# TinyDVR_Slave.net
KiCad netlist of a schematic drawn in Altium Designer
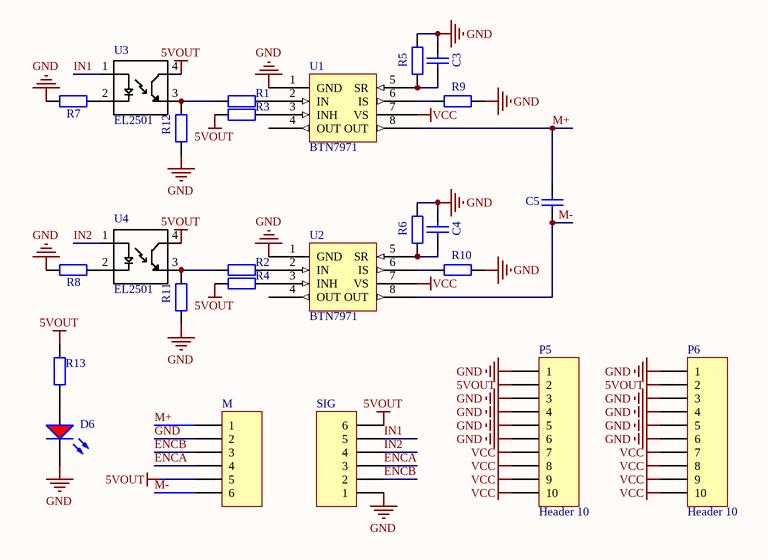
[diagram p0: TinyDVR_Slave.SchDoc]

(export (version "E")
  (design (tool "Eeschema 10.0.6"))
  (components
    (comp (ref "C3")
      (value "100nF (104) 10% 50V")
      (footprint "0603_C")
      (description "贴片电容")
      (libsource (lib "Miscellaneous Devices LC") (part "0603 100nF (104) 10% 50V"))
    )
    (comp (ref "C4")
      (value "100nF (104) 10% 50V")
      (footprint "0603_C")
      (description "贴片电容")
      (libsource (lib "Miscellaneous Devices LC") (part "0603 100nF (104) 10% 50V"))
    )
    (comp (ref "C5")
      (value "22pF (220) 5% 50V")
      (footprint "0603_C")
      (description "贴片电容")
      (libsource (lib "Miscellaneous Devices LC") (part "0603 22pF (220) 5% 50V"))
    )
    (comp (ref "D6")
      (value "红灯 0603")
      (footprint "0603_LED_S1")
      (description "发光二极管")
      (libsource (lib "Miscellaneous Devices LC") (part "0603 红灯"))
    )
    (comp (ref "M")
      (value "Header 6H")
      (footprint "HDR1X6H")
      (description "Header, 6-Pin, Right Angle")
      (fields (field (name "PUBLISHER") "Altium Limited"))
      (libsource (lib "") (part "Header 6H_1"))
    )
    (comp (ref "P5")
      (value "Header 10")
      (footprint "HDR1X10")
      (description "Header, 10-Pin")
      (fields (field (name "PUBLISHER") "Altium Limited"))
      (libsource (lib "Miscellaneous Connectors") (part "Header 10"))
    )
    (comp (ref "P6")
      (value "Header 10")
      (footprint "HDR1X10")
      (description "Header, 10-Pin")
      (fields (field (name "PUBLISHER") "Altium Limited"))
      (libsource (lib "Miscellaneous Connectors") (part "Header 10"))
    )
    (comp (ref "R1")
      (value "10KΩ (1002) ±1%")
      (footprint "0603_R")
      (description "贴片电阻")
      (libsource (lib "Miscellaneous Devices LC") (part "0603 10KΩ (1002) 1%"))
    )
    (comp (ref "R2")
      (value "10KΩ (1002) ±1%")
      (footprint "0603_R")
      (description "贴片电阻")
      (libsource (lib "Miscellaneous Devices LC") (part "0603 10KΩ (1002) 1%"))
    )
    (comp (ref "R3")
      (value "10KΩ (1002) ±1%")
      (footprint "0603_R")
      (description "贴片电阻")
      (libsource (lib "Miscellaneous Devices LC") (part "0603 10KΩ (1002) 1%"))
    )
    (comp (ref "R4")
      (value "10KΩ (1002) ±1%")
      (footprint "0603_R")
      (description "贴片电阻")
      (libsource (lib "Miscellaneous Devices LC") (part "0603 10KΩ (1002) 1%"))
    )
    (comp (ref "R5")
      (value "1KΩ (1001) ±1%")
      (footprint "0603_R")
      (description "贴片电阻")
      (libsource (lib "") (part "0603 1KΩ (1001) 1%_1"))
    )
    (comp (ref "R6")
      (value "1KΩ (1001) ±1%")
      (footprint "0603_R")
      (description "贴片电阻")
      (libsource (lib "") (part "0603 1KΩ (1001) 1%_1"))
    )
    (comp (ref "R7")
      (value "1KΩ (1001) ±1%")
      (footprint "0603_R")
      (description "贴片电阻")
      (libsource (lib "Miscellaneous Devices LC") (part "0603 1KΩ (1001) 1%"))
    )
    (comp (ref "R8")
      (value "1KΩ (1001) ±1%")
      (footprint "0603_R")
      (description "贴片电阻")
      (libsource (lib "Miscellaneous Devices LC") (part "0603 1KΩ (1001) 1%"))
    )
    (comp (ref "R9")
      (value "2KΩ (2001) ±1%")
      (footprint "0603_R")
      (description "贴片电阻")
      (libsource (lib "Miscellaneous Devices LC") (part "0603 2KΩ (2001) 1%"))
    )
    (comp (ref "R10")
      (value "2KΩ (2001) ±1%")
      (footprint "0603_R")
      (description "贴片电阻")
      (libsource (lib "Miscellaneous Devices LC") (part "0603 2KΩ (2001) 1%"))
    )
    (comp (ref "R11")
      (value "2KΩ (2001) ±1%")
      (footprint "0603_R")
      (description "贴片电阻")
      (libsource (lib "") (part "0603 2KΩ (2001) 1%_1"))
    )
    (comp (ref "R12")
      (value "2KΩ (2001) ±1%")
      (footprint "0603_R")
      (description "贴片电阻")
      (libsource (lib "") (part "0603 2KΩ (2001) 1%_1"))
    )
    (comp (ref "R13")
      (value "4.7k")
      (footprint "0603_R")
      (description "贴片电阻")
      (libsource (lib "Miscellaneous Devices LC") (part "0603 470Ω (4700) 1%"))
    )
    (comp (ref "SIG")
      (value "Header 6H")
      (footprint "HDR1X6H")
      (description "Header, 6-Pin, Right Angle")
      (fields (field (name "PUBLISHER") "Altium Limited"))
      (libsource (lib "Miscellaneous Connectors") (part "Header 6H"))
    )
    (comp (ref "U1")
      (value "BTN7971")
      (footprint "DPAK127P1615X127-8N")
      (libsource (lib "Sheet2") (part "BTN7971"))
    )
    (comp (ref "U2")
      (value "BTN7971")
      (footprint "DPAK127P1615X127-8N")
      (libsource (lib "Sheet2") (part "BTN7971"))
    )
    (comp (ref "U3")
      (value "EL2501")
      (footprint "*SOIC254P1030X390-4N_EL817S1(A)(TU)-V")
      (description "Optoisoltr 5kv Transistor 4-Smd")
      (fields (field (name "MF") "Everlight Electronics") (field (name "MP") "EL817S1_A__TU_-V"))
      (libsource (lib "altium-import") (part "root_0_EL817S1(A)(TU)-V_"))
    )
    (comp (ref "U4")
      (value "EL2501")
      (footprint "*SOIC254P1030X390-4N_EL817S1(A)(TU)-V")
      (description "Optoisoltr 5kv Transistor 4-Smd")
      (fields (field (name "MF") "Everlight Electronics") (field (name "MP") "EL817S1_A__TU_-V"))
      (libsource (lib "altium-import") (part "root_0_EL817S1(A)(TU)-V_"))
    )
  )
  (nets
    (net (code "1") (name "/ENCA") (class "Default")
      (node (ref "M") (pin "4") (pinfunction "4_4") (pintype "passive"))
      (node (ref "SIG") (pin "3") (pinfunction "3_3") (pintype "passive"))
    )
    (net (code "2") (name "/ENCB") (class "Default")
      (node (ref "M") (pin "3") (pinfunction "3_3") (pintype "passive"))
      (node (ref "SIG") (pin "2") (pinfunction "2_2") (pintype "passive"))
    )
    (net (code "3") (name "/IN1") (class "Default")
      (node (ref "SIG") (pin "5") (pinfunction "5_5") (pintype "passive"))
      (node (ref "U3") (pin "1") (pinfunction "A_1") (pintype "passive"))
    )
    (net (code "4") (name "/IN2") (class "Default")
      (node (ref "SIG") (pin "4") (pinfunction "4_4") (pintype "passive"))
      (node (ref "U4") (pin "1") (pinfunction "A_1") (pintype "passive"))
    )
    (net (code "5") (name "/M+") (class "Default")
      (node (ref "C5") (pin "2") (pinfunction "2_2") (pintype "passive"))
      (node (ref "M") (pin "1") (pinfunction "1_1") (pintype "passive"))
      (node (ref "U1") (pin "8") (pinfunction "OUT_8") (pintype "output"))
    )
    (net (code "6") (name "/M-") (class "Default")
      (node (ref "C5") (pin "1") (pinfunction "1_1") (pintype "passive"))
      (node (ref "M") (pin "6") (pinfunction "6_6") (pintype "passive"))
      (node (ref "U2") (pin "8") (pinfunction "OUT_8") (pintype "output"))
    )
    (net (code "7") (name "5VOUT") (class "Default")
      (node (ref "M") (pin "5") (pinfunction "5_5") (pintype "passive"))
      (node (ref "P5") (pin "2") (pinfunction "2_2") (pintype "passive"))
      (node (ref "P6") (pin "2") (pinfunction "2_2") (pintype "passive"))
      (node (ref "R13") (pin "2") (pinfunction "2_2") (pintype "passive"))
      (node (ref "R3") (pin "1") (pinfunction "1_1") (pintype "passive"))
      (node (ref "R4") (pin "1") (pinfunction "1_1") (pintype "passive"))
      (node (ref "SIG") (pin "6") (pinfunction "6_6") (pintype "passive"))
      (node (ref "U3") (pin "4") (pinfunction "CT_4") (pintype "passive"))
      (node (ref "U4") (pin "4") (pinfunction "CT_4") (pintype "passive"))
    )
    (net (code "8") (name "GND") (class "Default")
      (node (ref "C3") (pin "2") (pinfunction "2_2") (pintype "passive"))
      (node (ref "C4") (pin "2") (pinfunction "2_2") (pintype "passive"))
      (node (ref "D6") (pin "K") (pinfunction "K_K") (pintype "passive"))
      (node (ref "M") (pin "2") (pinfunction "2_2") (pintype "passive"))
      (node (ref "P5") (pin "1") (pinfunction "1_1") (pintype "passive"))
      (node (ref "P5") (pin "3") (pinfunction "3_3") (pintype "passive"))
      (node (ref "P5") (pin "4") (pinfunction "4_4") (pintype "passive"))
      (node (ref "P5") (pin "5") (pinfunction "5_5") (pintype "passive"))
      (node (ref "P5") (pin "6") (pinfunction "6_6") (pintype "passive"))
      (node (ref "P6") (pin "1") (pinfunction "1_1") (pintype "passive"))
      (node (ref "P6") (pin "3") (pinfunction "3_3") (pintype "passive"))
      (node (ref "P6") (pin "4") (pinfunction "4_4") (pintype "passive"))
      (node (ref "P6") (pin "5") (pinfunction "5_5") (pintype "passive"))
      (node (ref "P6") (pin "6") (pinfunction "6_6") (pintype "passive"))
      (node (ref "R10") (pin "1") (pinfunction "1_1") (pintype "passive"))
      (node (ref "R11") (pin "1") (pinfunction "1_1") (pintype "passive"))
      (node (ref "R12") (pin "1") (pinfunction "1_1") (pintype "passive"))
      (node (ref "R5") (pin "2") (pinfunction "2_2") (pintype "passive"))
      (node (ref "R6") (pin "2") (pinfunction "2_2") (pintype "passive"))
      (node (ref "R7") (pin "2") (pinfunction "2_2") (pintype "passive"))
      (node (ref "R8") (pin "2") (pinfunction "2_2") (pintype "passive"))
      (node (ref "R9") (pin "1") (pinfunction "1_1") (pintype "passive"))
      (node (ref "SIG") (pin "1") (pinfunction "1_1") (pintype "passive"))
      (node (ref "U1") (pin "1") (pinfunction "GND_1") (pintype "passive"))
      (node (ref "U2") (pin "1") (pinfunction "GND_1") (pintype "passive"))
    )
    (net (code "9") (name "Net-(D6-PadA)") (class "Default")
      (node (ref "D6") (pin "A") (pinfunction "A_A") (pintype "passive"))
      (node (ref "R13") (pin "1") (pinfunction "1_1") (pintype "passive"))
    )
    (net (code "10") (name "Net-(U1-IN)") (class "Default")
      (node (ref "R1") (pin "2") (pinfunction "2_2") (pintype "passive"))
      (node (ref "U1") (pin "2") (pinfunction "IN_2") (pintype "input"))
    )
    (net (code "11") (name "Net-(U1-INH)") (class "Default")
      (node (ref "R3") (pin "2") (pinfunction "2_2") (pintype "passive"))
      (node (ref "U1") (pin "3") (pinfunction "INH_3") (pintype "input"))
    )
    (net (code "12") (name "Net-(U1-IS)") (class "Default")
      (node (ref "R9") (pin "2") (pinfunction "2_2") (pintype "passive"))
      (node (ref "U1") (pin "6") (pinfunction "IS_6") (pintype "output"))
    )
    (net (code "13") (name "Net-(U1-SR)") (class "Default")
      (node (ref "C3") (pin "1") (pinfunction "1_1") (pintype "passive"))
      (node (ref "R5") (pin "1") (pinfunction "1_1") (pintype "passive"))
      (node (ref "U1") (pin "5") (pinfunction "SR_5") (pintype "input"))
    )
    (net (code "14") (name "Net-(U2-IN)") (class "Default")
      (node (ref "R2") (pin "2") (pinfunction "2_2") (pintype "passive"))
      (node (ref "U2") (pin "2") (pinfunction "IN_2") (pintype "input"))
    )
    (net (code "15") (name "Net-(U2-INH)") (class "Default")
      (node (ref "R4") (pin "2") (pinfunction "2_2") (pintype "passive"))
      (node (ref "U2") (pin "3") (pinfunction "INH_3") (pintype "input"))
    )
    (net (code "16") (name "Net-(U2-IS)") (class "Default")
      (node (ref "R10") (pin "2") (pinfunction "2_2") (pintype "passive"))
      (node (ref "U2") (pin "6") (pinfunction "IS_6") (pintype "output"))
    )
    (net (code "17") (name "Net-(U2-SR)") (class "Default")
      (node (ref "C4") (pin "1") (pinfunction "1_1") (pintype "passive"))
      (node (ref "R6") (pin "1") (pinfunction "1_1") (pintype "passive"))
      (node (ref "U2") (pin "5") (pinfunction "SR_5") (pintype "input"))
    )
    (net (code "18") (name "Net-(U3-C)") (class "Default")
      (node (ref "R7") (pin "1") (pinfunction "1_1") (pintype "passive"))
      (node (ref "U3") (pin "2") (pinfunction "C_2") (pintype "passive"))
    )
    (net (code "19") (name "Net-(U3-ET)") (class "Default")
      (node (ref "R1") (pin "1") (pinfunction "1_1") (pintype "passive"))
      (node (ref "R12") (pin "2") (pinfunction "2_2") (pintype "passive"))
      (node (ref "U3") (pin "3") (pinfunction "ET_3") (pintype "passive"))
    )
    (net (code "20") (name "Net-(U4-C)") (class "Default")
      (node (ref "R8") (pin "1") (pinfunction "1_1") (pintype "passive"))
      (node (ref "U4") (pin "2") (pinfunction "C_2") (pintype "passive"))
    )
    (net (code "21") (name "Net-(U4-ET)") (class "Default")
      (node (ref "R11") (pin "2") (pinfunction "2_2") (pintype "passive"))
      (node (ref "R2") (pin "1") (pinfunction "1_1") (pintype "passive"))
      (node (ref "U4") (pin "3") (pinfunction "ET_3") (pintype "passive"))
    )
    (net (code "22") (name "VCC") (class "Default")
      (node (ref "P5") (pin "10") (pinfunction "10_10") (pintype "passive"))
      (node (ref "P5") (pin "7") (pinfunction "7_7") (pintype "passive"))
      (node (ref "P5") (pin "8") (pinfunction "8_8") (pintype "passive"))
      (node (ref "P5") (pin "9") (pinfunction "9_9") (pintype "passive"))
      (node (ref "P6") (pin "10") (pinfunction "10_10") (pintype "passive"))
      (node (ref "P6") (pin "7") (pinfunction "7_7") (pintype "passive"))
      (node (ref "P6") (pin "8") (pinfunction "8_8") (pintype "passive"))
      (node (ref "P6") (pin "9") (pinfunction "9_9") (pintype "passive"))
      (node (ref "U1") (pin "7") (pinfunction "VS_7") (pintype "passive"))
      (node (ref "U2") (pin "7") (pinfunction "VS_7") (pintype "passive"))
    )
    (net (code "23") (name "unconnected-(U1-OUT-Pad4)") (class "Default")
      (node (ref "U1") (pin "4") (pinfunction "OUT_4") (pintype "output"))
    )
    (net (code "24") (name "unconnected-(U2-OUT-Pad4)") (class "Default")
      (node (ref "U2") (pin "4") (pinfunction "OUT_4") (pintype "output"))
    )
  )
)
